# VentaConnected_ESP8266_V0_01_2018-09-03_.net
KiCad netlist of a schematic drawn in EAGLE
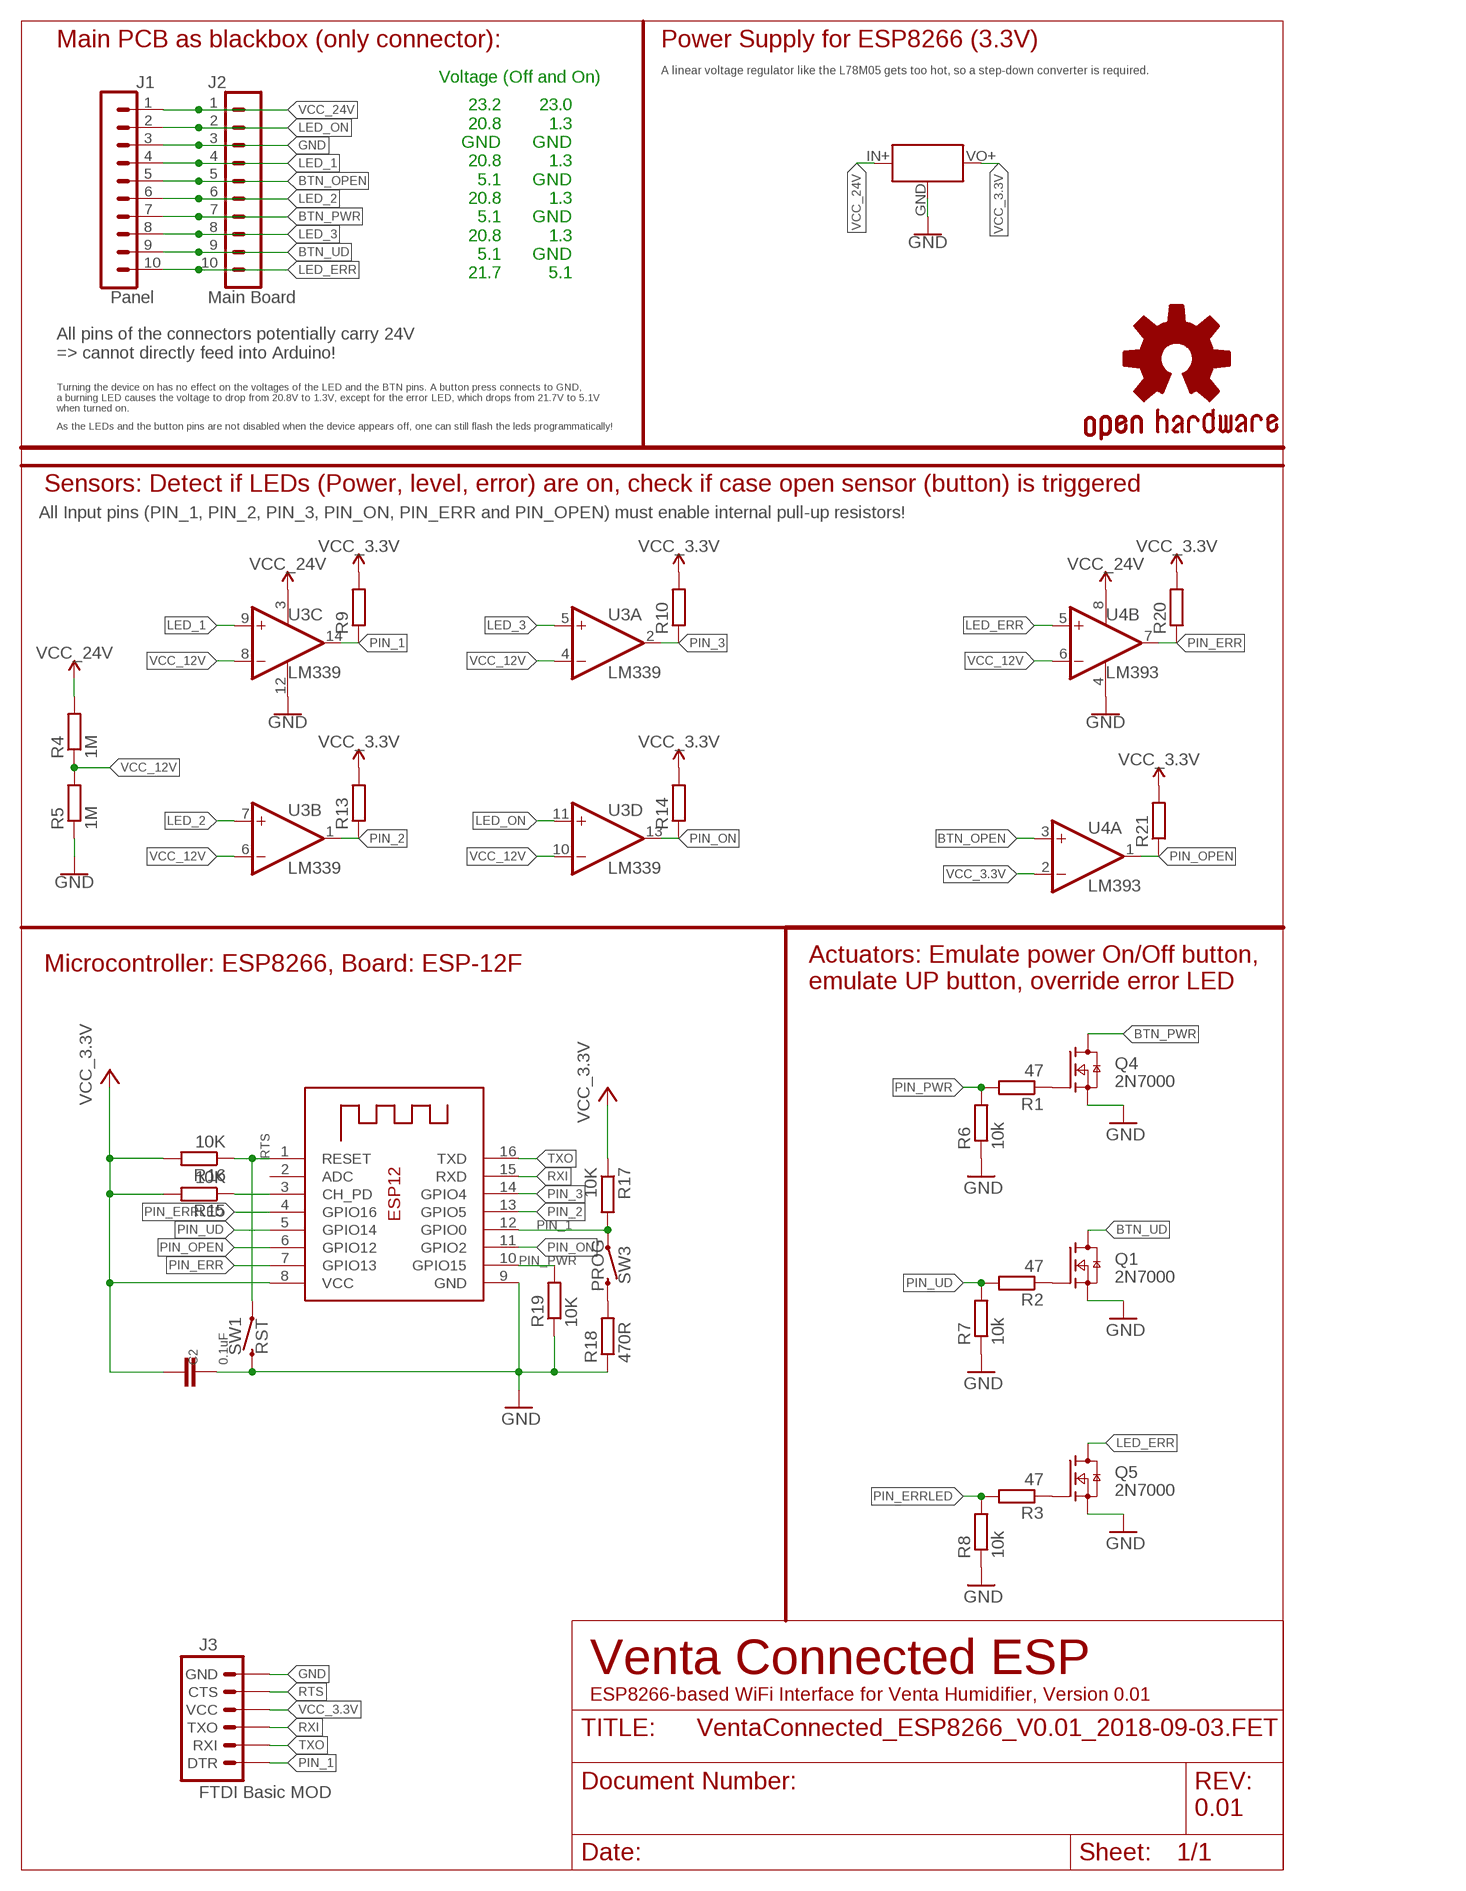
[diagram p0: schematic, sheet 1]

(export (version "E")
  (design (tool "Eeschema 10.0.6"))
  (components
    (comp (ref "C2")
      (value "0.1uF")
      (footprint "eagle-import:C0805")
      (libsource (lib "eagle-import") (part "C-EUC0805"))
    )
    (comp (ref "GOLD_ORB_SM1")
      (value "OSHWLOGO_GOLD_ORB_SM")
      (footprint "eagle-import:OSHW2")
      (libsource (lib "eagle-import") (part "OSHWLOGO_GOLD_ORB_SM"))
    )
    (comp (ref "J1")
      (value "Panel")
      (footprint "eagle-import:2X5-SHROUDED")
      (libsource (lib "eagle-import") (part "CONN_05X2SHD"))
    )
    (comp (ref "J2")
      (value "Main Board")
      (footprint "eagle-import:2X5")
      (libsource (lib "eagle-import") (part "CONN_05X2PTH"))
    )
    (comp (ref "J3")
      (value "FTDI Basic MOD")
      (footprint "eagle-import:1X06")
      (libsource (lib "eagle-import") (part "ARDUINO_SERIAL_PROGRAMPTH"))
    )
    (comp (ref "Q1")
      (value "2N7000")
      (footprint "eagle-import:SOT23")
      (libsource (lib "eagle-import") (part "2N7002E"))
    )
    (comp (ref "Q4")
      (value "2N7000")
      (footprint "eagle-import:SOT23")
      (libsource (lib "eagle-import") (part "2N7002E"))
    )
    (comp (ref "Q5")
      (value "2N7000")
      (footprint "eagle-import:SOT23")
      (libsource (lib "eagle-import") (part "2N7002E"))
    )
    (comp (ref "R1")
      (value "47")
      (footprint "eagle-import:R0805")
      (libsource (lib "eagle-import") (part "resistor_348_R-EU_R0805"))
    )
    (comp (ref "R2")
      (value "47")
      (footprint "eagle-import:R0805")
      (libsource (lib "eagle-import") (part "resistor_348_R-EU_R0805"))
    )
    (comp (ref "R3")
      (value "47")
      (footprint "eagle-import:R0805")
      (libsource (lib "eagle-import") (part "resistor_348_R-EU_R0805"))
    )
    (comp (ref "R4")
      (value "1M")
      (footprint "eagle-import:R0805")
      (libsource (lib "eagle-import") (part "resistor_348_R-EU_R0805"))
    )
    (comp (ref "R5")
      (value "1M")
      (footprint "eagle-import:R0805")
      (libsource (lib "eagle-import") (part "resistor_348_R-EU_R0805"))
    )
    (comp (ref "R6")
      (value "10k")
      (footprint "eagle-import:R0805")
      (libsource (lib "eagle-import") (part "resistor_348_R-EU_R0805"))
    )
    (comp (ref "R7")
      (value "10k")
      (footprint "eagle-import:R0805")
      (libsource (lib "eagle-import") (part "resistor_348_R-EU_R0805"))
    )
    (comp (ref "R8")
      (value "10k")
      (footprint "eagle-import:R0805")
      (libsource (lib "eagle-import") (part "resistor_348_R-EU_R0805"))
    )
    (comp (ref "R9")
      (value "R-EU_R0805")
      (footprint "eagle-import:R0805")
      (libsource (lib "eagle-import") (part "resistor_348_R-EU_R0805"))
    )
    (comp (ref "R10")
      (value "R-EU_R0805")
      (footprint "eagle-import:R0805")
      (libsource (lib "eagle-import") (part "resistor_348_R-EU_R0805"))
    )
    (comp (ref "R13")
      (value "R-EU_R0805")
      (footprint "eagle-import:R0805")
      (libsource (lib "eagle-import") (part "resistor_348_R-EU_R0805"))
    )
    (comp (ref "R14")
      (value "R-EU_R0805")
      (footprint "eagle-import:R0805")
      (libsource (lib "eagle-import") (part "resistor_348_R-EU_R0805"))
    )
    (comp (ref "R15")
      (value "10K")
      (footprint "eagle-import:R0805")
      (libsource (lib "eagle-import") (part "R-EU_R0805"))
    )
    (comp (ref "R16")
      (value "10K")
      (footprint "eagle-import:R0805")
      (libsource (lib "eagle-import") (part "R-EU_R0805"))
    )
    (comp (ref "R17")
      (value "10K")
      (footprint "eagle-import:R0805")
      (libsource (lib "eagle-import") (part "R-EU_R0805"))
    )
    (comp (ref "R18")
      (value "470R")
      (footprint "eagle-import:R0805")
      (libsource (lib "eagle-import") (part "R-EU_R0805"))
    )
    (comp (ref "R19")
      (value "10K")
      (footprint "eagle-import:R0805")
      (libsource (lib "eagle-import") (part "R-EU_R0805"))
    )
    (comp (ref "R20")
      (value "R-EU_R0805")
      (footprint "eagle-import:R0805")
      (libsource (lib "eagle-import") (part "resistor_348_R-EU_R0805"))
    )
    (comp (ref "R21")
      (value "R-EU_R0805")
      (footprint "eagle-import:R0805")
      (libsource (lib "eagle-import") (part "resistor_348_R-EU_R0805"))
    )
    (comp (ref "SW1")
      (value "RST")
      (footprint "eagle-import:TACTILE_SWITCH_SMD_6.0X3.5MM")
      (libsource (lib "eagle-import") (part "MOMENTARY-SWITCH-SPST-SMD-6.0X3.5MM"))
    )
    (comp (ref "SW3")
      (value "PROG")
      (footprint "eagle-import:TACTILE_SWITCH_SMD_6.0X3.5MM")
      (libsource (lib "eagle-import") (part "MOMENTARY-SWITCH-SPST-SMD-6.0X3.5MM"))
    )
    (comp (ref "U2")
      (value "3.3V_BUCK_CONVERTER")
      (footprint "eagle-import:MINI_BUCK_CONVERTER_UPDOWN")
      (libsource (lib "eagle-import") (part "MINI_BUCK_CONVERTER_UPSIDEDOWN"))
    )
    (comp (ref "U3")
      (value "LM339")
      (footprint "eagle-import:SO14")
      (libsource (lib "eagle-import") (part "TLC339D"))
    )
    (comp (ref "U4")
      (value "LM393")
      (footprint "eagle-import:SO08")
      (libsource (lib "eagle-import") (part "LM393D"))
    )
    (comp (ref "X2")
      (value "ESP-12e")
      (footprint "eagle-import:ESP-12")
      (libsource (lib "eagle-import") (part "ESP-12"))
    )
  )
  (nets
    (net (code "1") (name "BTN_OPEN") (class "Default")
      (node (ref "J1") (pin "5") (pinfunction "5_5") (pintype "passive"))
      (node (ref "J2") (pin "5") (pinfunction "5_5") (pintype "passive"))
      (node (ref "U4") (pin "3") (pinfunction "+IN_3") (pintype "input"))
    )
    (net (code "2") (name "BTN_PWR") (class "Default")
      (node (ref "J1") (pin "7") (pinfunction "7_7") (pintype "passive"))
      (node (ref "J2") (pin "7") (pinfunction "7_7") (pintype "passive"))
      (node (ref "Q4") (pin "3") (pinfunction "D_3") (pintype "passive"))
    )
    (net (code "3") (name "BTN_UD") (class "Default")
      (node (ref "J1") (pin "9") (pinfunction "9_9") (pintype "passive"))
      (node (ref "J2") (pin "9") (pinfunction "9_9") (pintype "passive"))
      (node (ref "Q1") (pin "3") (pinfunction "D_3") (pintype "passive"))
    )
    (net (code "4") (name "GND") (class "Default")
      (node (ref "C2") (pin "1") (pinfunction "1_1") (pintype "passive"))
      (node (ref "J1") (pin "3") (pinfunction "3_3") (pintype "passive"))
      (node (ref "J2") (pin "3") (pinfunction "3_3") (pintype "passive"))
      (node (ref "J3") (pin "6") (pinfunction "GND_6") (pintype "passive"))
      (node (ref "Q1") (pin "2") (pinfunction "S_2") (pintype "passive"))
      (node (ref "Q4") (pin "2") (pinfunction "S_2") (pintype "passive"))
      (node (ref "Q5") (pin "2") (pinfunction "S_2") (pintype "passive"))
      (node (ref "R18") (pin "1") (pinfunction "1_1") (pintype "passive"))
      (node (ref "R19") (pin "1") (pinfunction "1_1") (pintype "passive"))
      (node (ref "R5") (pin "1") (pinfunction "1_1") (pintype "passive"))
      (node (ref "R6") (pin "1") (pinfunction "1_1") (pintype "passive"))
      (node (ref "R7") (pin "1") (pinfunction "1_1") (pintype "passive"))
      (node (ref "R8") (pin "1") (pinfunction "1_1") (pintype "passive"))
      (node (ref "SW1") (pin "2") (pinfunction "2_2") (pintype "passive"))
      (node (ref "U2") (pin "GND") (pinfunction "GND_GND") (pintype "bidirectional"))
      (node (ref "U3") (pin "12") (pinfunction "V-_12") (pintype "power_in"))
      (node (ref "U4") (pin "4") (pinfunction "V-_4") (pintype "power_in"))
      (node (ref "X2") (pin "9") (pinfunction "GND_9") (pintype "power_in"))
    )
    (net (code "5") (name "LED_1") (class "Default")
      (node (ref "J1") (pin "4") (pinfunction "4_4") (pintype "passive"))
      (node (ref "J2") (pin "4") (pinfunction "4_4") (pintype "passive"))
      (node (ref "U3") (pin "9") (pinfunction "+IN_9") (pintype "input"))
    )
    (net (code "6") (name "LED_2") (class "Default")
      (node (ref "J1") (pin "6") (pinfunction "6_6") (pintype "passive"))
      (node (ref "J2") (pin "6") (pinfunction "6_6") (pintype "passive"))
      (node (ref "U3") (pin "7") (pinfunction "+IN_7") (pintype "input"))
    )
    (net (code "7") (name "LED_3") (class "Default")
      (node (ref "J1") (pin "8") (pinfunction "8_8") (pintype "passive"))
      (node (ref "J2") (pin "8") (pinfunction "8_8") (pintype "passive"))
      (node (ref "U3") (pin "5") (pinfunction "+IN_5") (pintype "input"))
    )
    (net (code "8") (name "LED_ERR") (class "Default")
      (node (ref "J1") (pin "10") (pinfunction "10_10") (pintype "passive"))
      (node (ref "J2") (pin "10") (pinfunction "10_10") (pintype "passive"))
      (node (ref "Q5") (pin "3") (pinfunction "D_3") (pintype "passive"))
      (node (ref "U4") (pin "5") (pinfunction "+IN_5") (pintype "input"))
    )
    (net (code "9") (name "LED_ON") (class "Default")
      (node (ref "J1") (pin "2") (pinfunction "2_2") (pintype "passive"))
      (node (ref "J2") (pin "2") (pinfunction "2_2") (pintype "passive"))
      (node (ref "U3") (pin "11") (pinfunction "+IN_11") (pintype "input"))
    )
    (net (code "10") (name "Net-(Q1-G)") (class "Default")
      (node (ref "Q1") (pin "1") (pinfunction "G_1") (pintype "passive"))
      (node (ref "R2") (pin "1") (pinfunction "1_1") (pintype "passive"))
    )
    (net (code "11") (name "Net-(Q4-G)") (class "Default")
      (node (ref "Q4") (pin "1") (pinfunction "G_1") (pintype "passive"))
      (node (ref "R1") (pin "1") (pinfunction "1_1") (pintype "passive"))
    )
    (net (code "12") (name "Net-(Q5-G)") (class "Default")
      (node (ref "Q5") (pin "1") (pinfunction "G_1") (pintype "passive"))
      (node (ref "R3") (pin "1") (pinfunction "1_1") (pintype "passive"))
    )
    (net (code "13") (name "Net-(R18-Pad2)") (class "Default")
      (node (ref "R18") (pin "2") (pinfunction "2_2") (pintype "passive"))
      (node (ref "SW3") (pin "2") (pinfunction "2_2") (pintype "passive"))
    )
    (net (code "14") (name "Net-(X2-CH_PD)") (class "Default")
      (node (ref "R15") (pin "1") (pinfunction "1_1") (pintype "passive"))
      (node (ref "X2") (pin "3") (pinfunction "CH_PD_3") (pintype "input"))
    )
    (net (code "15") (name "PIN_1") (class "Default")
      (node (ref "J3") (pin "1") (pinfunction "DTR_1") (pintype "passive"))
      (node (ref "R17") (pin "2") (pinfunction "2_2") (pintype "passive"))
      (node (ref "R9") (pin "1") (pinfunction "1_1") (pintype "passive"))
      (node (ref "SW3") (pin "1") (pinfunction "1_1") (pintype "passive"))
      (node (ref "U3") (pin "14") (pinfunction "OUT_14") (pintype "output"))
      (node (ref "X2") (pin "12") (pinfunction "GPIO0_12") (pintype "bidirectional"))
    )
    (net (code "16") (name "PIN_2") (class "Default")
      (node (ref "R13") (pin "1") (pinfunction "1_1") (pintype "passive"))
      (node (ref "U3") (pin "1") (pinfunction "OUT_1") (pintype "output"))
      (node (ref "X2") (pin "13") (pinfunction "GPIO5_13") (pintype "bidirectional"))
    )
    (net (code "17") (name "PIN_3") (class "Default")
      (node (ref "R10") (pin "1") (pinfunction "1_1") (pintype "passive"))
      (node (ref "U3") (pin "2") (pinfunction "OUT_2") (pintype "output"))
      (node (ref "X2") (pin "14") (pinfunction "GPIO4_14") (pintype "bidirectional"))
    )
    (net (code "18") (name "PIN_ERR") (class "Default")
      (node (ref "R20") (pin "1") (pinfunction "1_1") (pintype "passive"))
      (node (ref "U4") (pin "7") (pinfunction "OUT_7") (pintype "output"))
      (node (ref "X2") (pin "7") (pinfunction "GPIO13_7") (pintype "bidirectional"))
    )
    (net (code "19") (name "PIN_ERRLED") (class "Default")
      (node (ref "R3") (pin "2") (pinfunction "2_2") (pintype "passive"))
      (node (ref "R8") (pin "2") (pinfunction "2_2") (pintype "passive"))
      (node (ref "X2") (pin "4") (pinfunction "GPIO16_4") (pintype "bidirectional"))
    )
    (net (code "20") (name "PIN_ON") (class "Default")
      (node (ref "R14") (pin "1") (pinfunction "1_1") (pintype "passive"))
      (node (ref "U3") (pin "13") (pinfunction "OUT_13") (pintype "output"))
      (node (ref "X2") (pin "11") (pinfunction "GPIO2_11") (pintype "bidirectional"))
    )
    (net (code "21") (name "PIN_OPEN") (class "Default")
      (node (ref "R21") (pin "1") (pinfunction "1_1") (pintype "passive"))
      (node (ref "U4") (pin "1") (pinfunction "OUT_1") (pintype "output"))
      (node (ref "X2") (pin "6") (pinfunction "GPIO12_6") (pintype "bidirectional"))
    )
    (net (code "22") (name "PIN_PWR") (class "Default")
      (node (ref "R1") (pin "2") (pinfunction "2_2") (pintype "passive"))
      (node (ref "R19") (pin "2") (pinfunction "2_2") (pintype "passive"))
      (node (ref "R6") (pin "2") (pinfunction "2_2") (pintype "passive"))
      (node (ref "X2") (pin "10") (pinfunction "GPIO15_10") (pintype "bidirectional"))
    )
    (net (code "23") (name "PIN_UD") (class "Default")
      (node (ref "R2") (pin "2") (pinfunction "2_2") (pintype "passive"))
      (node (ref "R7") (pin "2") (pinfunction "2_2") (pintype "passive"))
      (node (ref "X2") (pin "5") (pinfunction "GPIO14_5") (pintype "bidirectional"))
    )
    (net (code "24") (name "RTS") (class "Default")
      (node (ref "J3") (pin "5") (pinfunction "CTS_5") (pintype "passive"))
      (node (ref "R16") (pin "1") (pinfunction "1_1") (pintype "passive"))
      (node (ref "SW1") (pin "1") (pinfunction "1_1") (pintype "passive"))
      (node (ref "X2") (pin "1") (pinfunction "RESET_1") (pintype "input"))
    )
    (net (code "25") (name "RXI") (class "Default")
      (node (ref "J3") (pin "3") (pinfunction "TXO_3") (pintype "passive"))
      (node (ref "X2") (pin "15") (pinfunction "RXD_15") (pintype "input"))
    )
    (net (code "26") (name "TXO") (class "Default")
      (node (ref "J3") (pin "2") (pinfunction "RXI_2") (pintype "passive"))
      (node (ref "X2") (pin "16") (pinfunction "TXD_16") (pintype "output"))
    )
    (net (code "27") (name "VCC_3.3V") (class "Default")
      (node (ref "C2") (pin "2") (pinfunction "2_2") (pintype "passive"))
      (node (ref "J3") (pin "4") (pinfunction "VCC_4") (pintype "passive"))
      (node (ref "R10") (pin "2") (pinfunction "2_2") (pintype "passive"))
      (node (ref "R13") (pin "2") (pinfunction "2_2") (pintype "passive"))
      (node (ref "R14") (pin "2") (pinfunction "2_2") (pintype "passive"))
      (node (ref "R15") (pin "2") (pinfunction "2_2") (pintype "passive"))
      (node (ref "R16") (pin "2") (pinfunction "2_2") (pintype "passive"))
      (node (ref "R17") (pin "1") (pinfunction "1_1") (pintype "passive"))
      (node (ref "R20") (pin "2") (pinfunction "2_2") (pintype "passive"))
      (node (ref "R21") (pin "2") (pinfunction "2_2") (pintype "passive"))
      (node (ref "R9") (pin "2") (pinfunction "2_2") (pintype "passive"))
      (node (ref "U2") (pin "VO+") (pinfunction "VOUT_VO+") (pintype "power_in"))
      (node (ref "U4") (pin "2") (pinfunction "-IN_2") (pintype "input"))
      (node (ref "X2") (pin "8") (pinfunction "VCC_8") (pintype "power_in"))
    )
    (net (code "28") (name "VCC_12V") (class "Default")
      (node (ref "R4") (pin "1") (pinfunction "1_1") (pintype "passive"))
      (node (ref "R5") (pin "2") (pinfunction "2_2") (pintype "passive"))
      (node (ref "U3") (pin "10") (pinfunction "-IN_10") (pintype "input"))
      (node (ref "U3") (pin "4") (pinfunction "-IN_4") (pintype "input"))
      (node (ref "U3") (pin "6") (pinfunction "-IN_6") (pintype "input"))
      (node (ref "U3") (pin "8") (pinfunction "-IN_8") (pintype "input"))
      (node (ref "U4") (pin "6") (pinfunction "-IN_6") (pintype "input"))
    )
    (net (code "29") (name "VCC_24V") (class "Default")
      (node (ref "J1") (pin "1") (pinfunction "1_1") (pintype "passive"))
      (node (ref "J2") (pin "1") (pinfunction "1_1") (pintype "passive"))
      (node (ref "R4") (pin "2") (pinfunction "2_2") (pintype "passive"))
      (node (ref "U2") (pin "IN+") (pinfunction "VIN_IN+") (pintype "input"))
      (node (ref "U3") (pin "3") (pinfunction "V+_3") (pintype "power_in"))
      (node (ref "U4") (pin "8") (pinfunction "V+_8") (pintype "power_in"))
    )
    (net (code "30") (name "unconnected-(X2-ADC-Pad2)") (class "Default")
      (node (ref "X2") (pin "2") (pinfunction "ADC_2") (pintype "passive"))
    )
  )
)
